# color_sensor_node.net
KiCad netlist of a schematic drawn in EAGLE
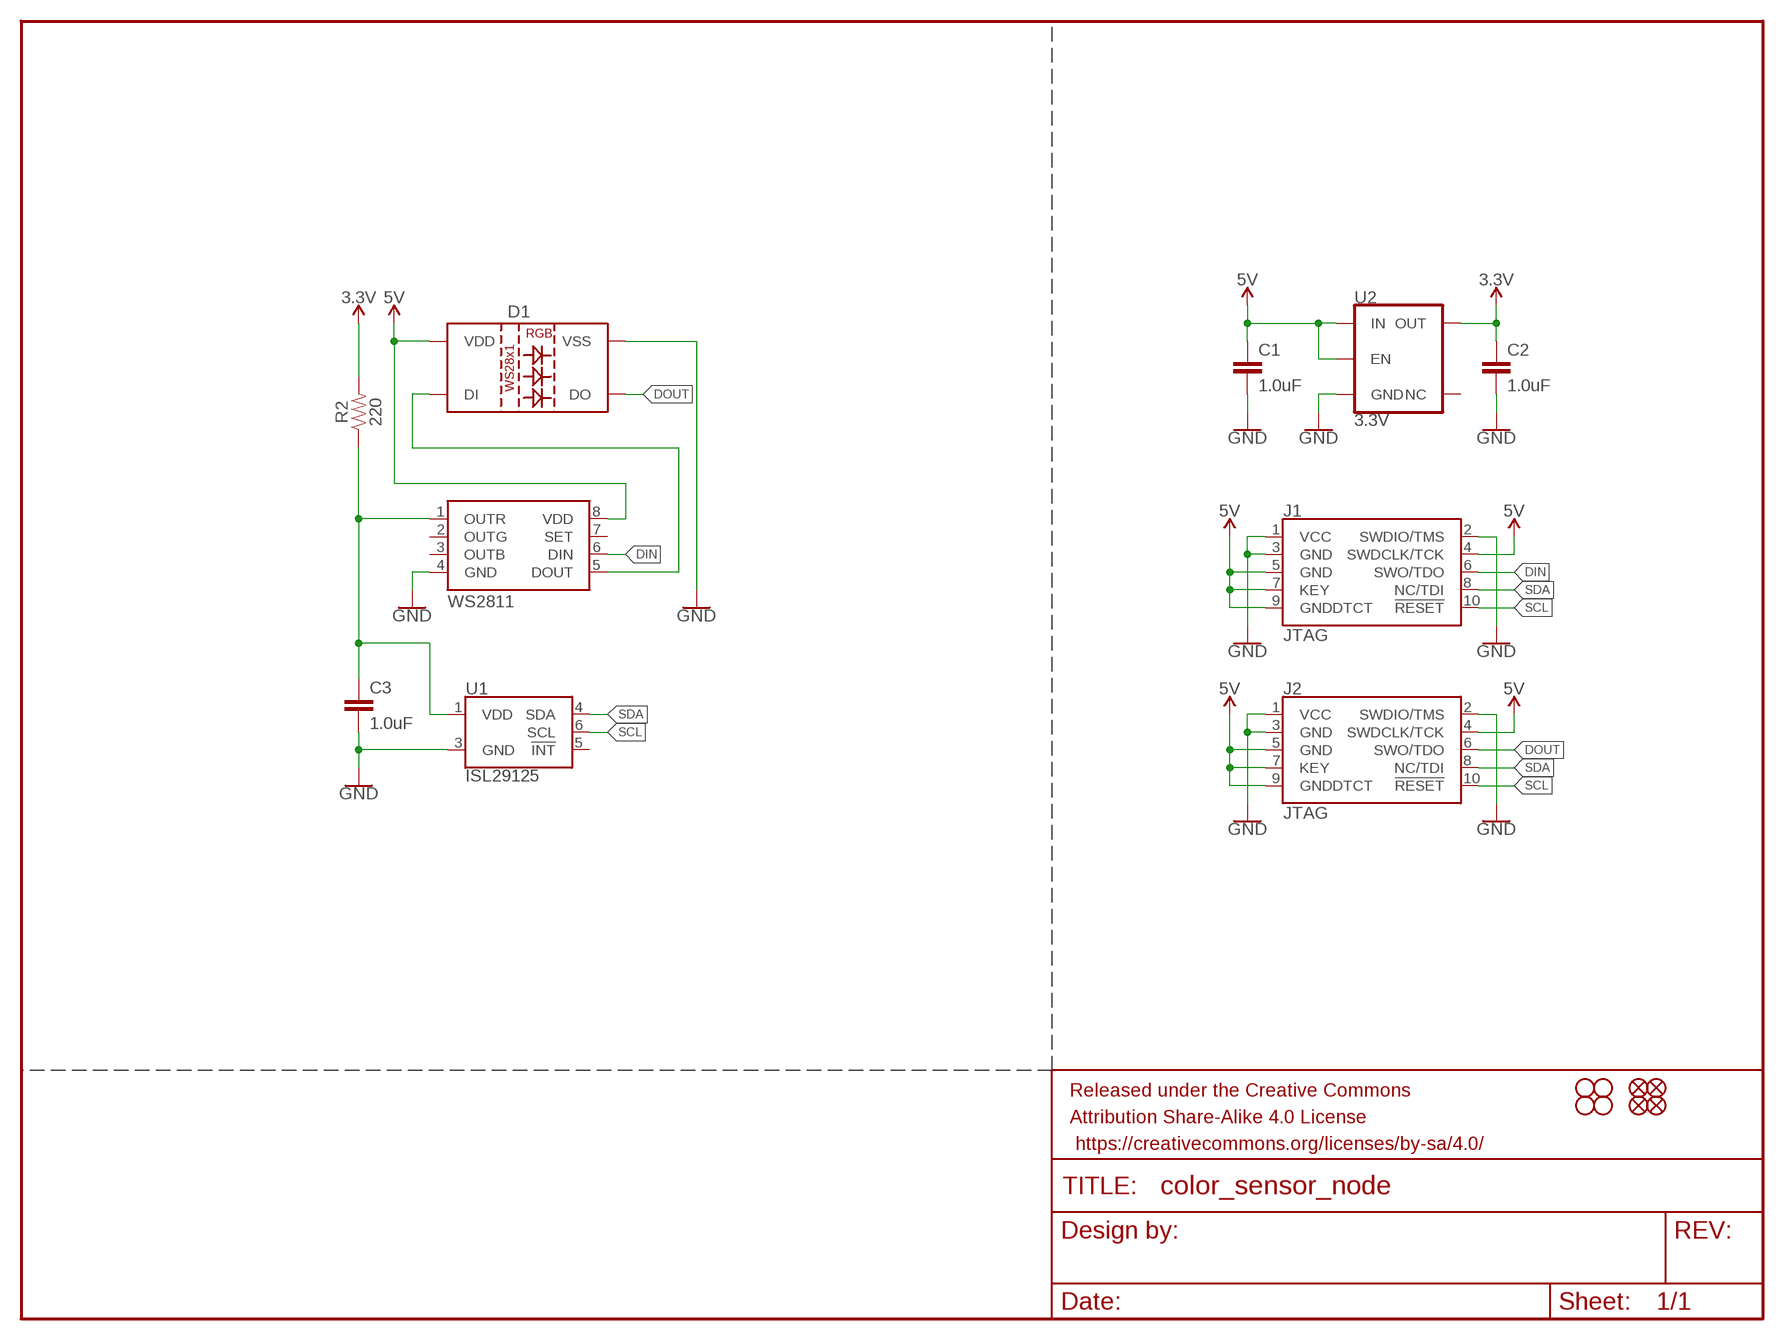
[diagram p0: schematic, sheet 1]

(export (version "E")
  (design (tool "Eeschema 10.0.6"))
  (components
    (comp (ref "C1")
      (value "1.0uF")
      (footprint "eagle-import:0603")
      (libsource (lib "eagle-import") (part "1.0UF-0603-16V-10%"))
    )
    (comp (ref "C2")
      (value "1.0uF")
      (footprint "eagle-import:0603")
      (libsource (lib "eagle-import") (part "1.0UF-0603-16V-10%"))
    )
    (comp (ref "C3")
      (value "1.0uF")
      (footprint "eagle-import:0603")
      (libsource (lib "eagle-import") (part "1.0UF-0603-16V-10%"))
    )
    (comp (ref "D1")
      (value "WS2812B")
      (footprint "eagle-import:WS2812-2020")
      (libsource (lib "eagle-import") (part "WS2812-2020"))
    )
    (comp (ref "FD1")
      (value "FIDUCIAL1X2")
      (footprint "eagle-import:FIDUCIAL-1X2")
      (libsource (lib "eagle-import") (part "FIDUCIAL1X2"))
    )
    (comp (ref "FD2")
      (value "FIDUCIAL1X2")
      (footprint "eagle-import:FIDUCIAL-1X2")
      (libsource (lib "eagle-import") (part "FIDUCIAL1X2"))
    )
    (comp (ref "FD3")
      (value "FIDUCIAL1X2")
      (footprint "eagle-import:FIDUCIAL-1X2")
      (libsource (lib "eagle-import") (part "FIDUCIAL1X2"))
    )
    (comp (ref "FD4")
      (value "FIDUCIAL1X2")
      (footprint "eagle-import:FIDUCIAL-1X2")
      (libsource (lib "eagle-import") (part "FIDUCIAL1X2"))
    )
    (comp (ref "FRAME1")
      (value "FRAME-LETTER")
      (footprint "eagle-import:CREATIVE_COMMONS")
      (libsource (lib "eagle-import") (part "FRAME-LETTER"))
    )
    (comp (ref "H1")
      (value "STAND-OFF")
      (footprint "eagle-import:STAND-OFF")
      (libsource (lib "eagle-import") (part "STAND-OFF"))
    )
    (comp (ref "H2")
      (value "STAND-OFF")
      (footprint "eagle-import:STAND-OFF")
      (libsource (lib "eagle-import") (part "STAND-OFF"))
    )
    (comp (ref "H3")
      (value "STAND-OFF")
      (footprint "eagle-import:STAND-OFF")
      (libsource (lib "eagle-import") (part "STAND-OFF"))
    )
    (comp (ref "H4")
      (value "STAND-OFF")
      (footprint "eagle-import:STAND-OFF")
      (libsource (lib "eagle-import") (part "STAND-OFF"))
    )
    (comp (ref "J1")
      (value "JTAG")
      (footprint "eagle-import:2X5-SMD-1.27MM")
      (libsource (lib "eagle-import") (part "CORTEX_JTAG_DEBUG_SMD"))
    )
    (comp (ref "J2")
      (value "JTAG")
      (footprint "eagle-import:2X5-SMD-1.27MM")
      (libsource (lib "eagle-import") (part "CORTEX_JTAG_DEBUG_SMD"))
    )
    (comp (ref "R2")
      (value "220")
      (footprint "eagle-import:0603")
      (libsource (lib "eagle-import") (part "220OHM-0603-1/10W-1%"))
    )
    (comp (ref "U1")
      (value "ISL29125")
      (footprint "eagle-import:ODFN-6")
      (libsource (lib "eagle-import") (part "ISL29125"))
    )
    (comp (ref "U2")
      (value "3.3V")
      (footprint "eagle-import:SOT23-5")
      (libsource (lib "eagle-import") (part "V_REG_AP2112K-3.3V"))
    )
    (comp (ref "U3")
      (value "WS2811")
      (footprint "eagle-import:SOIC-8")
      (libsource (lib "eagle-import") (part "WS2811"))
    )
  )
  (nets
    (net (code "1") (name "3.3V") (class "Default")
      (node (ref "C2") (pin "1") (pinfunction "1_1") (pintype "passive"))
      (node (ref "R2") (pin "2") (pinfunction "2_2") (pintype "passive"))
      (node (ref "U2") (pin "5") (pinfunction "OUT_5") (pintype "passive"))
    )
    (net (code "2") (name "5V") (class "Default")
      (node (ref "C1") (pin "1") (pinfunction "1_1") (pintype "passive"))
      (node (ref "D1") (pin "4") (pinfunction "VDD_4") (pintype "bidirectional"))
      (node (ref "J1") (pin "4") (pinfunction "SWDCLK/TCK_4") (pintype "bidirectional"))
      (node (ref "J1") (pin "5") (pinfunction "GND_5") (pintype "bidirectional"))
      (node (ref "J1") (pin "7") (pinfunction "KEY_7") (pintype "bidirectional"))
      (node (ref "J1") (pin "9") (pinfunction "GNDDTCT_9") (pintype "bidirectional"))
      (node (ref "J2") (pin "4") (pinfunction "SWDCLK/TCK_4") (pintype "bidirectional"))
      (node (ref "J2") (pin "5") (pinfunction "GND_5") (pintype "bidirectional"))
      (node (ref "J2") (pin "7") (pinfunction "KEY_7") (pintype "bidirectional"))
      (node (ref "J2") (pin "9") (pinfunction "GNDDTCT_9") (pintype "bidirectional"))
      (node (ref "U2") (pin "1") (pinfunction "IN_1") (pintype "input"))
      (node (ref "U2") (pin "3") (pinfunction "EN_3") (pintype "input"))
      (node (ref "U3") (pin "8") (pinfunction "VDD_8") (pintype "bidirectional"))
    )
    (net (code "3") (name "DIN") (class "Default")
      (node (ref "J1") (pin "6") (pinfunction "SWO/TDO_6") (pintype "bidirectional"))
      (node (ref "U3") (pin "6") (pinfunction "DIN_6") (pintype "bidirectional"))
    )
    (net (code "4") (name "DOUT") (class "Default")
      (node (ref "D1") (pin "1") (pinfunction "DO_1") (pintype "bidirectional"))
      (node (ref "J2") (pin "6") (pinfunction "SWO/TDO_6") (pintype "bidirectional"))
    )
    (net (code "5") (name "GND") (class "Default")
      (node (ref "C1") (pin "2") (pinfunction "2_2") (pintype "passive"))
      (node (ref "C2") (pin "2") (pinfunction "2_2") (pintype "passive"))
      (node (ref "C3") (pin "2") (pinfunction "2_2") (pintype "passive"))
      (node (ref "D1") (pin "2") (pinfunction "VSS_2") (pintype "bidirectional"))
      (node (ref "J1") (pin "1") (pinfunction "VCC_1") (pintype "bidirectional"))
      (node (ref "J1") (pin "2") (pinfunction "SWDIO/TMS_2") (pintype "bidirectional"))
      (node (ref "J1") (pin "3") (pinfunction "GND_3") (pintype "bidirectional"))
      (node (ref "J2") (pin "1") (pinfunction "VCC_1") (pintype "bidirectional"))
      (node (ref "J2") (pin "2") (pinfunction "SWDIO/TMS_2") (pintype "bidirectional"))
      (node (ref "J2") (pin "3") (pinfunction "GND_3") (pintype "bidirectional"))
      (node (ref "U1") (pin "3") (pinfunction "GND_3") (pintype "bidirectional"))
      (node (ref "U2") (pin "2") (pinfunction "GND_2") (pintype "input"))
      (node (ref "U3") (pin "4") (pinfunction "GND_4") (pintype "bidirectional"))
    )
    (net (code "6") (name "Net-(D1-DI)") (class "Default")
      (node (ref "D1") (pin "3") (pinfunction "DI_3") (pintype "bidirectional"))
      (node (ref "U3") (pin "5") (pinfunction "DOUT_5") (pintype "bidirectional"))
    )
    (net (code "7") (name "Net-(U1-VDD)") (class "Default")
      (node (ref "C3") (pin "1") (pinfunction "1_1") (pintype "passive"))
      (node (ref "R2") (pin "1") (pinfunction "1_1") (pintype "passive"))
      (node (ref "U1") (pin "1") (pinfunction "VDD_1") (pintype "bidirectional"))
      (node (ref "U3") (pin "1") (pinfunction "OUTR_1") (pintype "bidirectional"))
    )
    (net (code "8") (name "SCL") (class "Default")
      (node (ref "J1") (pin "10") (pinfunction "~{RESET}_10") (pintype "bidirectional"))
      (node (ref "J2") (pin "10") (pinfunction "~{RESET}_10") (pintype "bidirectional"))
      (node (ref "U1") (pin "6") (pinfunction "SCL_6") (pintype "bidirectional"))
    )
    (net (code "9") (name "SDA") (class "Default")
      (node (ref "J1") (pin "8") (pinfunction "NC/TDI_8") (pintype "bidirectional"))
      (node (ref "J2") (pin "8") (pinfunction "NC/TDI_8") (pintype "bidirectional"))
      (node (ref "U1") (pin "4") (pinfunction "SDA_4") (pintype "bidirectional"))
    )
    (net (code "10") (name "unconnected-(U1-~{INT}-Pad5)") (class "Default")
      (node (ref "U1") (pin "5") (pinfunction "~{INT}_5") (pintype "bidirectional"))
    )
    (net (code "11") (name "unconnected-(U2-NC-Pad4)") (class "Default")
      (node (ref "U2") (pin "4") (pinfunction "NC_4") (pintype "no_connect"))
    )
    (net (code "12") (name "unconnected-(U3-OUTB-Pad3)") (class "Default")
      (node (ref "U3") (pin "3") (pinfunction "OUTB_3") (pintype "bidirectional"))
    )
    (net (code "13") (name "unconnected-(U3-OUTG-Pad2)") (class "Default")
      (node (ref "U3") (pin "2") (pinfunction "OUTG_2") (pintype "bidirectional"))
    )
    (net (code "14") (name "unconnected-(U3-SET-Pad7)") (class "Default")
      (node (ref "U3") (pin "7") (pinfunction "SET_7") (pintype "bidirectional"))
    )
  )
)
